# usb-audio.net
KiCad netlist of a schematic drawn in EAGLE
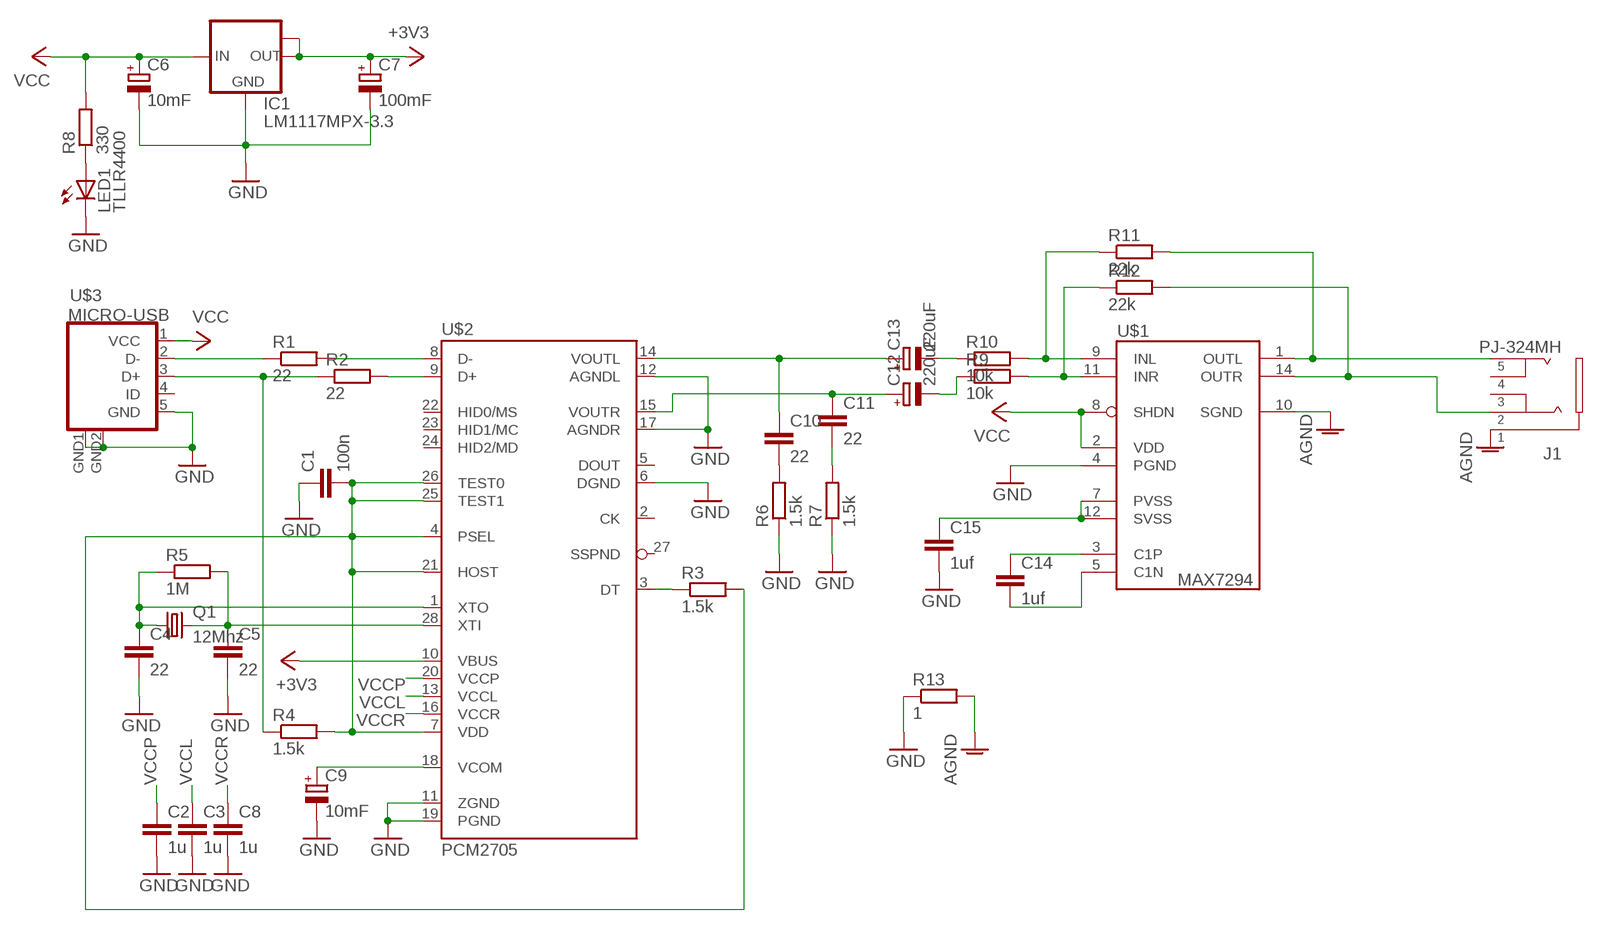
[diagram p0: schematic, sheet 1]

(export (version "E")
  (design (tool "Eeschema 10.0.6"))
  (components
    (comp (ref "C1")
      (value "100n")
      (footprint "eagle-import:C0805")
      (libsource (lib "eagle-import") (part "C-EUC0805"))
    )
    (comp (ref "C2")
      (value "1u")
      (footprint "eagle-import:C0805")
      (libsource (lib "eagle-import") (part "C-EUC0805"))
    )
    (comp (ref "C3")
      (value "1u")
      (footprint "eagle-import:C0805")
      (libsource (lib "eagle-import") (part "C-EUC0805"))
    )
    (comp (ref "C4")
      (value "22")
      (footprint "eagle-import:C0805")
      (libsource (lib "eagle-import") (part "C-EUC0805"))
    )
    (comp (ref "C5")
      (value "22")
      (footprint "eagle-import:C0805")
      (libsource (lib "eagle-import") (part "C-EUC0805"))
    )
    (comp (ref "C6")
      (value "10mF")
      (footprint "eagle-import:CT3216")
      (libsource (lib "eagle-import") (part "CPOL-EUCT3216"))
    )
    (comp (ref "C7")
      (value "100mF")
      (footprint "eagle-import:CT3216")
      (libsource (lib "eagle-import") (part "CPOL-EUCT3216"))
    )
    (comp (ref "C8")
      (value "1u")
      (footprint "eagle-import:C0805")
      (libsource (lib "eagle-import") (part "C-EUC0805"))
    )
    (comp (ref "C9")
      (value "10mF")
      (footprint "eagle-import:CT3216")
      (libsource (lib "eagle-import") (part "CPOL-EUCT3216"))
    )
    (comp (ref "C10")
      (value "22")
      (footprint "eagle-import:C0805")
      (libsource (lib "eagle-import") (part "C-EUC0805"))
    )
    (comp (ref "C11")
      (value "22")
      (footprint "eagle-import:C0805")
      (libsource (lib "eagle-import") (part "C-EUC0805"))
    )
    (comp (ref "C12")
      (value "220uF")
      (footprint "eagle-import:E2-5")
      (libsource (lib "eagle-import") (part "CPOL-EUE2-5"))
    )
    (comp (ref "C13")
      (value "220uF")
      (footprint "eagle-import:E2-5")
      (libsource (lib "eagle-import") (part "CPOL-EUE2-5"))
    )
    (comp (ref "C14")
      (value "1uf")
      (footprint "eagle-import:C0805")
      (libsource (lib "eagle-import") (part "C-EUC0805"))
    )
    (comp (ref "C15")
      (value "1uf")
      (footprint "eagle-import:C0805")
      (libsource (lib "eagle-import") (part "C-EUC0805"))
    )
    (comp (ref "IC1")
      (value "LM1117MPX-3.3")
      (footprint "eagle-import:SOT223")
      (libsource (lib "eagle-import") (part "LM1117MPX-3.3"))
    )
    (comp (ref "J1")
      (value "PJ-324MH")
      (footprint "eagle-import:PJ-324MH")
      (libsource (lib "eagle-import") (part "PJ-324MH"))
    )
    (comp (ref "LED1")
      (value "TLLR4400")
      (footprint "eagle-import:LED3MM")
      (fields (field (name "MF") "VISHAY SEMICONDUCTOR"))
      (libsource (lib "eagle-import") (part "TLLR4400"))
    )
    (comp (ref "Q1")
      (value "12Mhz")
      (footprint "eagle-import:HC49_S")
      (libsource (lib "eagle-import") (part "CRYSTALHC49S"))
    )
    (comp (ref "R1")
      (value "22")
      (footprint "eagle-import:R0805")
      (libsource (lib "eagle-import") (part "R-EU_R0805"))
    )
    (comp (ref "R2")
      (value "22")
      (footprint "eagle-import:R0805")
      (libsource (lib "eagle-import") (part "R-EU_R0805"))
    )
    (comp (ref "R3")
      (value "1.5k")
      (footprint "eagle-import:R0805")
      (libsource (lib "eagle-import") (part "R-EU_R0805"))
    )
    (comp (ref "R4")
      (value "1.5k")
      (footprint "eagle-import:R0805")
      (libsource (lib "eagle-import") (part "R-EU_R0805"))
    )
    (comp (ref "R5")
      (value "1M")
      (footprint "eagle-import:R0805")
      (libsource (lib "eagle-import") (part "R-EU_R0805"))
    )
    (comp (ref "R6")
      (value "1.5k")
      (footprint "eagle-import:R0805")
      (libsource (lib "eagle-import") (part "R-EU_R0805"))
    )
    (comp (ref "R7")
      (value "1.5k")
      (footprint "eagle-import:R0805")
      (libsource (lib "eagle-import") (part "R-EU_R0805"))
    )
    (comp (ref "R8")
      (value "330")
      (footprint "eagle-import:R0805")
      (libsource (lib "eagle-import") (part "R-EU_R0805"))
    )
    (comp (ref "R9")
      (value "10k")
      (footprint "eagle-import:R0805")
      (libsource (lib "eagle-import") (part "R-EU_R0805"))
    )
    (comp (ref "R10")
      (value "10k")
      (footprint "eagle-import:R0805")
      (libsource (lib "eagle-import") (part "R-EU_R0805"))
    )
    (comp (ref "R11")
      (value "22k")
      (footprint "eagle-import:R0805")
      (libsource (lib "eagle-import") (part "R-EU_R0805"))
    )
    (comp (ref "R12")
      (value "22k")
      (footprint "eagle-import:R0805")
      (libsource (lib "eagle-import") (part "R-EU_R0805"))
    )
    (comp (ref "R13")
      (value "1")
      (footprint "eagle-import:R0805")
      (libsource (lib "eagle-import") (part "R-EU_R0805"))
    )
    (comp (ref "U$1")
      (value "MAX9724AEUD+")
      (footprint "eagle-import:TSSOP14")
      (libsource (lib "eagle-import") (part "MAX9724AEUD+"))
    )
    (comp (ref "U$2")
      (value "PCM2705")
      (footprint "eagle-import:SSOP28")
      (libsource (lib "eagle-import") (part "PCM2705"))
    )
    (comp (ref "U$3")
      (value "MICRO-USB")
      (footprint "eagle-import:MICRO-USB")
      (libsource (lib "eagle-import") (part "MICRO-USB"))
    )
  )
  (nets
    (net (code "1") (name "+3V3") (class "Default")
      (node (ref "C7") (pin "+") (pinfunction "+_+") (pintype "passive"))
      (node (ref "IC1") (pin "2") (pinfunction "OUT_2") (pintype "passive"))
      (node (ref "IC1") (pin "TAB") (pinfunction "OUT1_TAB") (pintype "passive"))
      (node (ref "U$2") (pin "10") (pinfunction "VBUS_10") (pintype "power_in"))
    )
    (net (code "2") (name "/VCCL") (class "Default")
      (node (ref "C3") (pin "1") (pinfunction "1_1") (pintype "passive"))
      (node (ref "U$2") (pin "13") (pinfunction "VCCL_13") (pintype "power_in"))
    )
    (net (code "3") (name "/VCCP") (class "Default")
      (node (ref "C2") (pin "1") (pinfunction "1_1") (pintype "passive"))
      (node (ref "U$2") (pin "20") (pinfunction "VCCP_20") (pintype "power_in"))
    )
    (net (code "4") (name "/VCCR") (class "Default")
      (node (ref "C8") (pin "1") (pinfunction "1_1") (pintype "passive"))
      (node (ref "U$2") (pin "16") (pinfunction "VCCR_16") (pintype "power_in"))
    )
    (net (code "5") (name "AGND") (class "Default")
      (node (ref "J1") (pin "1") (pinfunction "1_1") (pintype "passive"))
      (node (ref "R13") (pin "2") (pinfunction "2_2") (pintype "passive"))
      (node (ref "U$1") (pin "10") (pinfunction "SGND_10") (pintype "power_in"))
    )
    (net (code "6") (name "GND") (class "Default")
      (node (ref "C1") (pin "1") (pinfunction "1_1") (pintype "passive"))
      (node (ref "C15") (pin "2") (pinfunction "2_2") (pintype "passive"))
      (node (ref "C2") (pin "2") (pinfunction "2_2") (pintype "passive"))
      (node (ref "C3") (pin "2") (pinfunction "2_2") (pintype "passive"))
      (node (ref "C4") (pin "2") (pinfunction "2_2") (pintype "passive"))
      (node (ref "C5") (pin "2") (pinfunction "2_2") (pintype "passive"))
      (node (ref "C6") (pin "-") (pinfunction "-_-") (pintype "passive"))
      (node (ref "C7") (pin "-") (pinfunction "-_-") (pintype "passive"))
      (node (ref "C8") (pin "2") (pinfunction "2_2") (pintype "passive"))
      (node (ref "C9") (pin "-") (pinfunction "-_-") (pintype "passive"))
      (node (ref "IC1") (pin "1") (pinfunction "GND_1") (pintype "input"))
      (node (ref "LED1") (pin "K") (pinfunction "C_K") (pintype "passive"))
      (node (ref "R13") (pin "1") (pinfunction "1_1") (pintype "passive"))
      (node (ref "R6") (pin "1") (pinfunction "1_1") (pintype "passive"))
      (node (ref "R7") (pin "1") (pinfunction "1_1") (pintype "passive"))
      (node (ref "U$1") (pin "4") (pinfunction "PGND_4") (pintype "power_in"))
      (node (ref "U$2") (pin "11") (pinfunction "ZGND_11") (pintype "power_in"))
      (node (ref "U$2") (pin "12") (pinfunction "AGNDL_12") (pintype "power_in"))
      (node (ref "U$2") (pin "17") (pinfunction "AGNDR_17") (pintype "power_in"))
      (node (ref "U$2") (pin "19") (pinfunction "PGND_19") (pintype "power_in"))
      (node (ref "U$2") (pin "6") (pinfunction "DGND_6") (pintype "power_in"))
      (node (ref "U$3") (pin "5") (pinfunction "GND_5") (pintype "power_in"))
      (node (ref "U$3") (pin "GND1") (pinfunction "GND_GND1") (pintype "power_in"))
      (node (ref "U$3") (pin "GND2") (pinfunction "GND_GND2") (pintype "power_in"))
    )
    (net (code "7") (name "Net-(C10-Pad2)") (class "Default")
      (node (ref "C10") (pin "2") (pinfunction "2_2") (pintype "passive"))
      (node (ref "R6") (pin "2") (pinfunction "2_2") (pintype "passive"))
    )
    (net (code "8") (name "Net-(C11-Pad2)") (class "Default")
      (node (ref "C11") (pin "2") (pinfunction "2_2") (pintype "passive"))
      (node (ref "R7") (pin "2") (pinfunction "2_2") (pintype "passive"))
    )
    (net (code "9") (name "Net-(C12-Pad-)") (class "Default")
      (node (ref "C12") (pin "-") (pinfunction "-_-") (pintype "passive"))
      (node (ref "R9") (pin "1") (pinfunction "1_1") (pintype "passive"))
    )
    (net (code "10") (name "Net-(C13-Pad-)") (class "Default")
      (node (ref "C13") (pin "-") (pinfunction "-_-") (pintype "passive"))
      (node (ref "R10") (pin "1") (pinfunction "1_1") (pintype "passive"))
    )
    (net (code "11") (name "Net-(LED1-PadA)") (class "Default")
      (node (ref "LED1") (pin "A") (pinfunction "A_A") (pintype "passive"))
      (node (ref "R8") (pin "1") (pinfunction "1_1") (pintype "passive"))
    )
    (net (code "12") (name "Net-(U$1-C1N)") (class "Default")
      (node (ref "C14") (pin "2") (pinfunction "2_2") (pintype "passive"))
      (node (ref "U$1") (pin "5") (pinfunction "C1N_5") (pintype "bidirectional"))
    )
    (net (code "13") (name "Net-(U$1-C1P)") (class "Default")
      (node (ref "C14") (pin "1") (pinfunction "1_1") (pintype "passive"))
      (node (ref "U$1") (pin "3") (pinfunction "C1P_3") (pintype "bidirectional"))
    )
    (net (code "14") (name "Net-(U$1-INL)") (class "Default")
      (node (ref "R10") (pin "2") (pinfunction "2_2") (pintype "passive"))
      (node (ref "R11") (pin "1") (pinfunction "1_1") (pintype "passive"))
      (node (ref "U$1") (pin "9") (pinfunction "INL_9") (pintype "input"))
    )
    (net (code "15") (name "Net-(U$1-INR)") (class "Default")
      (node (ref "R12") (pin "1") (pinfunction "1_1") (pintype "passive"))
      (node (ref "R9") (pin "2") (pinfunction "2_2") (pintype "passive"))
      (node (ref "U$1") (pin "11") (pinfunction "INR_11") (pintype "input"))
    )
    (net (code "16") (name "Net-(U$1-OUTL)") (class "Default")
      (node (ref "J1") (pin "5") (pinfunction "5_5") (pintype "passive"))
      (node (ref "R11") (pin "2") (pinfunction "2_2") (pintype "passive"))
      (node (ref "U$1") (pin "1") (pinfunction "OUTL_1") (pintype "output"))
    )
    (net (code "17") (name "Net-(U$1-OUTR)") (class "Default")
      (node (ref "J1") (pin "2") (pinfunction "2_2") (pintype "passive"))
      (node (ref "R12") (pin "2") (pinfunction "2_2") (pintype "passive"))
      (node (ref "U$1") (pin "14") (pinfunction "OUTR_14") (pintype "output"))
    )
    (net (code "18") (name "Net-(U$1-PVSS)") (class "Default")
      (node (ref "C15") (pin "1") (pinfunction "1_1") (pintype "passive"))
      (node (ref "U$1") (pin "12") (pinfunction "SVSS_12") (pintype "power_in"))
      (node (ref "U$1") (pin "7") (pinfunction "PVSS_7") (pintype "output"))
    )
    (net (code "19") (name "Net-(U$2-D+)") (class "Default")
      (node (ref "R2") (pin "2") (pinfunction "2_2") (pintype "passive"))
      (node (ref "U$2") (pin "9") (pinfunction "D+_9") (pintype "bidirectional"))
    )
    (net (code "20") (name "Net-(U$2-D-)") (class "Default")
      (node (ref "R1") (pin "2") (pinfunction "2_2") (pintype "passive"))
      (node (ref "U$2") (pin "8") (pinfunction "D-_8") (pintype "bidirectional"))
    )
    (net (code "21") (name "Net-(U$2-DT)") (class "Default")
      (node (ref "R3") (pin "1") (pinfunction "1_1") (pintype "passive"))
      (node (ref "U$2") (pin "3") (pinfunction "DT_3") (pintype "bidirectional"))
    )
    (net (code "22") (name "Net-(U$2-HOST)") (class "Default")
      (node (ref "C1") (pin "2") (pinfunction "2_2") (pintype "passive"))
      (node (ref "R3") (pin "2") (pinfunction "2_2") (pintype "passive"))
      (node (ref "R4") (pin "2") (pinfunction "2_2") (pintype "passive"))
      (node (ref "U$2") (pin "21") (pinfunction "HOST_21") (pintype "input"))
      (node (ref "U$2") (pin "25") (pinfunction "TEST1_25") (pintype "input"))
      (node (ref "U$2") (pin "26") (pinfunction "TEST0_26") (pintype "input"))
      (node (ref "U$2") (pin "4") (pinfunction "PSEL_4") (pintype "input"))
      (node (ref "U$2") (pin "7") (pinfunction "VDD_7") (pintype "power_in"))
    )
    (net (code "23") (name "Net-(U$2-VCOM)") (class "Default")
      (node (ref "C9") (pin "+") (pinfunction "+_+") (pintype "passive"))
      (node (ref "U$2") (pin "18") (pinfunction "VCOM_18") (pintype "power_in"))
    )
    (net (code "24") (name "Net-(U$2-VOUTL)") (class "Default")
      (node (ref "C10") (pin "1") (pinfunction "1_1") (pintype "passive"))
      (node (ref "C13") (pin "+") (pinfunction "+_+") (pintype "passive"))
      (node (ref "U$2") (pin "14") (pinfunction "VOUTL_14") (pintype "output"))
    )
    (net (code "25") (name "Net-(U$2-VOUTR)") (class "Default")
      (node (ref "C11") (pin "1") (pinfunction "1_1") (pintype "passive"))
      (node (ref "C12") (pin "+") (pinfunction "+_+") (pintype "passive"))
      (node (ref "U$2") (pin "15") (pinfunction "VOUTR_15") (pintype "output"))
    )
    (net (code "26") (name "Net-(U$2-XTI)") (class "Default")
      (node (ref "C5") (pin "1") (pinfunction "1_1") (pintype "passive"))
      (node (ref "Q1") (pin "2") (pinfunction "2_2") (pintype "passive"))
      (node (ref "R5") (pin "2") (pinfunction "2_2") (pintype "passive"))
      (node (ref "U$2") (pin "28") (pinfunction "XTI_28") (pintype "input"))
    )
    (net (code "27") (name "Net-(U$2-XTO)") (class "Default")
      (node (ref "C4") (pin "1") (pinfunction "1_1") (pintype "passive"))
      (node (ref "Q1") (pin "1") (pinfunction "1_1") (pintype "passive"))
      (node (ref "R5") (pin "1") (pinfunction "1_1") (pintype "passive"))
      (node (ref "U$2") (pin "1") (pinfunction "XTO_1") (pintype "output"))
    )
    (net (code "28") (name "Net-(U$3-D+)") (class "Default")
      (node (ref "R2") (pin "1") (pinfunction "1_1") (pintype "passive"))
      (node (ref "R4") (pin "1") (pinfunction "1_1") (pintype "passive"))
      (node (ref "U$3") (pin "3") (pinfunction "D+_3") (pintype "bidirectional"))
    )
    (net (code "29") (name "Net-(U$3-D-)") (class "Default")
      (node (ref "R1") (pin "1") (pinfunction "1_1") (pintype "passive"))
      (node (ref "U$3") (pin "2") (pinfunction "D-_2") (pintype "bidirectional"))
    )
    (net (code "30") (name "VCC") (class "Default")
      (node (ref "C6") (pin "+") (pinfunction "+_+") (pintype "passive"))
      (node (ref "IC1") (pin "3") (pinfunction "IN_3") (pintype "input"))
      (node (ref "R8") (pin "2") (pinfunction "2_2") (pintype "passive"))
      (node (ref "U$1") (pin "2") (pinfunction "VDD_2") (pintype "power_in"))
      (node (ref "U$1") (pin "8") (pinfunction "SHDN_8") (pintype "input"))
      (node (ref "U$3") (pin "1") (pinfunction "VCC_1") (pintype "power_in"))
    )
    (net (code "31") (name "unconnected-(J1-Pad3)") (class "Default")
      (node (ref "J1") (pin "3") (pinfunction "3_3") (pintype "passive"))
    )
    (net (code "32") (name "unconnected-(J1-Pad4)") (class "Default")
      (node (ref "J1") (pin "4") (pinfunction "4_4") (pintype "passive"))
    )
    (net (code "33") (name "unconnected-(U$2-CK-Pad2)") (class "Default")
      (node (ref "U$2") (pin "2") (pinfunction "CK_2") (pintype "output"))
    )
    (net (code "34") (name "unconnected-(U$2-DOUT-Pad5)") (class "Default")
      (node (ref "U$2") (pin "5") (pinfunction "DOUT_5") (pintype "output"))
    )
    (net (code "35") (name "unconnected-(U$2-HID0{slash}MS-Pad22)") (class "Default")
      (node (ref "U$2") (pin "22") (pinfunction "HID0/MS_22") (pintype "input"))
    )
    (net (code "36") (name "unconnected-(U$2-HID1{slash}MC-Pad23)") (class "Default")
      (node (ref "U$2") (pin "23") (pinfunction "HID1/MC_23") (pintype "input"))
    )
    (net (code "37") (name "unconnected-(U$2-HID2{slash}MD-Pad24)") (class "Default")
      (node (ref "U$2") (pin "24") (pinfunction "HID2/MD_24") (pintype "input"))
    )
    (net (code "38") (name "unconnected-(U$2-SSPND-Pad27)") (class "Default")
      (node (ref "U$2") (pin "27") (pinfunction "SSPND_27") (pintype "output"))
    )
    (net (code "39") (name "unconnected-(U$3-ID-Pad4)") (class "Default")
      (node (ref "U$3") (pin "4") (pinfunction "ID_4") (pintype "bidirectional"))
    )
  )
)
